# heatingHeader.net
KiCad netlist of a schematic drawn in EAGLE
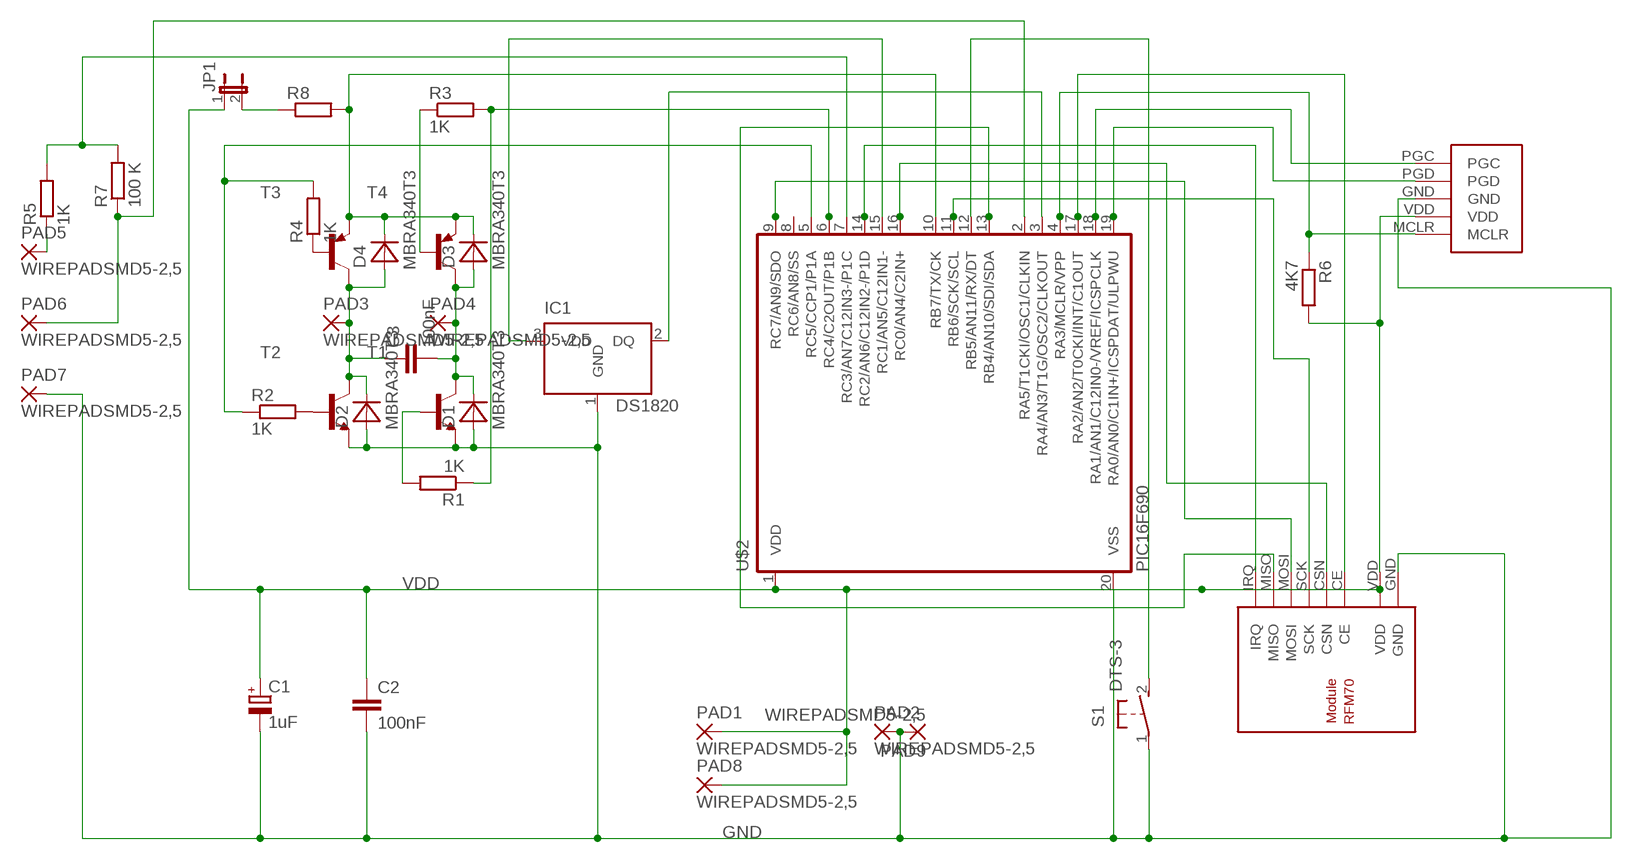
[diagram p0: schematic, sheet 1]

(export (version "E")
  (design (tool "Eeschema 10.0.6"))
  (components
    (comp (ref "C1")
      (value "1uF")
      (footprint "eagle-import:SMC_A")
      (libsource (lib "eagle-import") (part "CPOL-EUSMCA"))
    )
    (comp (ref "C2")
      (value "100nF")
      (footprint "eagle-import:C2012")
      (libsource (lib "eagle-import") (part "C-EUC2012"))
    )
    (comp (ref "C3")
      (value "100nF")
      (footprint "eagle-import:C2012")
      (libsource (lib "eagle-import") (part "C-EUC2012"))
    )
    (comp (ref "D1")
      (value "MBRA340T3")
      (footprint "eagle-import:SMA")
      (libsource (lib "eagle-import") (part "MBRA340T3"))
    )
    (comp (ref "D2")
      (value "MBRA340T3")
      (footprint "eagle-import:SMA")
      (libsource (lib "eagle-import") (part "MBRA340T3"))
    )
    (comp (ref "D3")
      (value "MBRA340T3")
      (footprint "eagle-import:SMA")
      (libsource (lib "eagle-import") (part "MBRA340T3"))
    )
    (comp (ref "D4")
      (value "MBRA340T3")
      (footprint "eagle-import:SMA")
      (libsource (lib "eagle-import") (part "MBRA340T3"))
    )
    (comp (ref "IC1")
      (value "DS1820")
      (footprint "eagle-import:TO-92")
      (libsource (lib "eagle-import") (part "DS1820"))
    )
    (comp (ref "JP1")
      (value "JP1E")
      (footprint "eagle-import:JP1")
      (libsource (lib "eagle-import") (part "JP1E"))
    )
    (comp (ref "PAD1")
      (value "WIREPADSMD5-2,5")
      (footprint "eagle-import:5-2,5")
      (libsource (lib "eagle-import") (part "WIREPADSMD5-2,5"))
    )
    (comp (ref "PAD2")
      (value "WIREPADSMD5-2,5")
      (footprint "eagle-import:5-2,5")
      (libsource (lib "eagle-import") (part "WIREPADSMD5-2,5"))
    )
    (comp (ref "PAD3")
      (value "WIREPADSMD5-2,5")
      (footprint "eagle-import:5-2,5")
      (libsource (lib "eagle-import") (part "WIREPADSMD5-2,5"))
    )
    (comp (ref "PAD4")
      (value "WIREPADSMD5-2,5")
      (footprint "eagle-import:5-2,5")
      (libsource (lib "eagle-import") (part "WIREPADSMD5-2,5"))
    )
    (comp (ref "PAD5")
      (value "WIREPADSMD5-2,5")
      (footprint "eagle-import:5-2,5")
      (libsource (lib "eagle-import") (part "WIREPADSMD5-2,5"))
    )
    (comp (ref "PAD6")
      (value "WIREPADSMD5-2,5")
      (footprint "eagle-import:5-2,5")
      (libsource (lib "eagle-import") (part "WIREPADSMD5-2,5"))
    )
    (comp (ref "PAD7")
      (value "WIREPADSMD5-2,5")
      (footprint "eagle-import:5-2,5")
      (libsource (lib "eagle-import") (part "WIREPADSMD5-2,5"))
    )
    (comp (ref "PAD8")
      (value "WIREPADSMD5-2,5")
      (footprint "eagle-import:5-2,5")
      (libsource (lib "eagle-import") (part "WIREPADSMD5-2,5"))
    )
    (comp (ref "PAD9")
      (value "WIREPADSMD5-2,5")
      (footprint "eagle-import:5-2,5")
      (libsource (lib "eagle-import") (part "WIREPADSMD5-2,5"))
    )
    (comp (ref "R1")
      (value "1K")
      (footprint "eagle-import:R1206")
      (libsource (lib "eagle-import") (part "R-EU_R1206"))
    )
    (comp (ref "R2")
      (value "1K")
      (footprint "eagle-import:R1206")
      (libsource (lib "eagle-import") (part "R-EU_R1206"))
    )
    (comp (ref "R3")
      (value "1K")
      (footprint "eagle-import:R1206")
      (libsource (lib "eagle-import") (part "R-EU_R1206"))
    )
    (comp (ref "R4")
      (value "1K")
      (footprint "eagle-import:R1206")
      (libsource (lib "eagle-import") (part "R-EU_R1206"))
    )
    (comp (ref "R5")
      (value "1K")
      (footprint "eagle-import:R1206")
      (libsource (lib "eagle-import") (part "R-EU_R1206"))
    )
    (comp (ref "R6")
      (value "4K7")
      (footprint "eagle-import:R1206W")
      (libsource (lib "eagle-import") (part "R-EU_R1206W"))
    )
    (comp (ref "R7")
      (value "100 K")
      (footprint "eagle-import:R1206")
      (libsource (lib "eagle-import") (part "R-EU_R1206"))
    )
    (comp (ref "R8")
      (value "R-EU_R2512W")
      (footprint "eagle-import:R2512W")
      (libsource (lib "eagle-import") (part "R-EU_R2512W"))
    )
    (comp (ref "S1")
      (value "DTS-3")
      (footprint "eagle-import:DTS-3")
      (libsource (lib "eagle-import") (part "DTS-3"))
    )
    (comp (ref "T1")
      (value "BC817-40-NPN-SOT23-BEC")
      (footprint "eagle-import:SOT23-BEC")
      (libsource (lib "eagle-import") (part "-NPN-SOT23-BECBC817-40"))
    )
    (comp (ref "T2")
      (value "BC817-40-NPN-SOT23-BEC")
      (footprint "eagle-import:SOT23-BEC")
      (libsource (lib "eagle-import") (part "-NPN-SOT23-BECBC817-40"))
    )
    (comp (ref "T3")
      (value "BC807-16-PNP-SOT23-BEC")
      (footprint "eagle-import:SOT23-BEC")
      (libsource (lib "eagle-import") (part "-PNP-SOT23-BECBC807-16"))
    )
    (comp (ref "T4")
      (value "BC807-16-PNP-SOT23-BEC")
      (footprint "eagle-import:SOT23-BEC")
      (libsource (lib "eagle-import") (part "-PNP-SOT23-BECBC807-16"))
    )
    (comp (ref "U$1")
      (value "RFM70")
      (footprint "eagle-import:RFM70")
      (libsource (lib "eagle-import") (part "RFM70"))
    )
    (comp (ref "U$2")
      (value "PIC16F690")
      (footprint "eagle-import:SSOP20")
      (libsource (lib "eagle-import") (part "PIC16F690"))
    )
    (comp (ref "U$3")
      (value "PROGRAMMINGHEADERDIP")
      (footprint "eagle-import:PROGHEADER")
      (libsource (lib "eagle-import") (part "PROGRAMMINGHEADERDIP"))
    )
  )
  (nets
    (net (code "1") (name "/GND") (class "Default")
      (node (ref "C1") (pin "-") (pinfunction "-_-") (pintype "passive"))
      (node (ref "C2") (pin "2") (pinfunction "2_2") (pintype "passive"))
      (node (ref "D1") (pin "A") (pinfunction "A_A") (pintype "passive"))
      (node (ref "D2") (pin "A") (pinfunction "A_A") (pintype "passive"))
      (node (ref "IC1") (pin "1") (pinfunction "GND_1") (pintype "power_in"))
      (node (ref "PAD2") (pin "1") (pinfunction "P_1") (pintype "passive"))
      (node (ref "PAD7") (pin "1") (pinfunction "P_1") (pintype "passive"))
      (node (ref "PAD9") (pin "1") (pinfunction "P_1") (pintype "passive"))
      (node (ref "S1") (pin "1") (pinfunction "1_1") (pintype "passive"))
      (node (ref "T1") (pin "E") (pinfunction "E_E") (pintype "passive"))
      (node (ref "T2") (pin "E") (pinfunction "E_E") (pintype "passive"))
      (node (ref "U$1") (pin "GND") (pinfunction "GND_GND") (pintype "power_in"))
      (node (ref "U$2") (pin "20") (pinfunction "VSS_20") (pintype "power_in"))
      (node (ref "U$3") (pin "GND") (pinfunction "GND_GND") (pintype "power_in"))
    )
    (net (code "2") (name "/VDD") (class "Default")
      (node (ref "C1") (pin "+") (pinfunction "+_+") (pintype "passive"))
      (node (ref "C2") (pin "1") (pinfunction "1_1") (pintype "passive"))
      (node (ref "JP1") (pin "1") (pinfunction "1_1") (pintype "passive"))
      (node (ref "PAD1") (pin "1") (pinfunction "P_1") (pintype "passive"))
      (node (ref "PAD8") (pin "1") (pinfunction "P_1") (pintype "passive"))
      (node (ref "R6") (pin "2") (pinfunction "2_2") (pintype "passive"))
      (node (ref "U$1") (pin "VDD") (pinfunction "VDD_VDD") (pintype "power_in"))
      (node (ref "U$2") (pin "1") (pinfunction "VDD_1") (pintype "power_in"))
      (node (ref "U$3") (pin "VDD") (pinfunction "VDD_VDD") (pintype "power_in"))
    )
    (net (code "3") (name "Net-(IC1-DQ)") (class "Default")
      (node (ref "IC1") (pin "2") (pinfunction "DQ_2") (pintype "output"))
      (node (ref "U$2") (pin "3") (pinfunction "RA4/AN3/T1G/OSC2/CLKOUT_3") (pintype "bidirectional"))
    )
    (net (code "4") (name "Net-(IC1-VDD)") (class "Default")
      (node (ref "IC1") (pin "3") (pinfunction "VDD_3") (pintype "input"))
      (node (ref "U$2") (pin "15") (pinfunction "RC1/AN5/C12IN1-_15") (pintype "bidirectional"))
    )
    (net (code "5") (name "Net-(JP1-Pad2)") (class "Default")
      (node (ref "JP1") (pin "2") (pinfunction "2_2") (pintype "passive"))
      (node (ref "R8") (pin "1") (pinfunction "1_1") (pintype "passive"))
    )
    (net (code "6") (name "Net-(PAD3-P)") (class "Default")
      (node (ref "C3") (pin "1") (pinfunction "1_1") (pintype "passive"))
      (node (ref "D2") (pin "C") (pinfunction "C_C") (pintype "passive"))
      (node (ref "D4") (pin "A") (pinfunction "A_A") (pintype "passive"))
      (node (ref "PAD3") (pin "1") (pinfunction "P_1") (pintype "passive"))
      (node (ref "T2") (pin "C") (pinfunction "C_C") (pintype "passive"))
      (node (ref "T3") (pin "C") (pinfunction "C_C") (pintype "passive"))
    )
    (net (code "7") (name "Net-(PAD4-P)") (class "Default")
      (node (ref "C3") (pin "2") (pinfunction "2_2") (pintype "passive"))
      (node (ref "D1") (pin "C") (pinfunction "C_C") (pintype "passive"))
      (node (ref "D3") (pin "A") (pinfunction "A_A") (pintype "passive"))
      (node (ref "PAD4") (pin "1") (pinfunction "P_1") (pintype "passive"))
      (node (ref "T1") (pin "C") (pinfunction "C_C") (pintype "passive"))
      (node (ref "T4") (pin "C") (pinfunction "C_C") (pintype "passive"))
    )
    (net (code "8") (name "Net-(PAD5-P)") (class "Default")
      (node (ref "PAD5") (pin "1") (pinfunction "P_1") (pintype "passive"))
      (node (ref "R5") (pin "1") (pinfunction "1_1") (pintype "passive"))
    )
    (net (code "9") (name "Net-(PAD6-P)") (class "Default")
      (node (ref "PAD6") (pin "1") (pinfunction "P_1") (pintype "passive"))
      (node (ref "R7") (pin "1") (pinfunction "1_1") (pintype "passive"))
      (node (ref "U$2") (pin "2") (pinfunction "RA5/T1CKI/OSC1/CLKIN_2") (pintype "bidirectional"))
    )
    (net (code "10") (name "Net-(R1-Pad2)") (class "Default")
      (node (ref "R1") (pin "2") (pinfunction "2_2") (pintype "passive"))
      (node (ref "T1") (pin "B") (pinfunction "B_B") (pintype "passive"))
    )
    (net (code "11") (name "Net-(R2-Pad2)") (class "Default")
      (node (ref "R2") (pin "2") (pinfunction "2_2") (pintype "passive"))
      (node (ref "T2") (pin "B") (pinfunction "B_B") (pintype "passive"))
    )
    (net (code "12") (name "Net-(R3-Pad1)") (class "Default")
      (node (ref "R3") (pin "1") (pinfunction "1_1") (pintype "passive"))
      (node (ref "T4") (pin "B") (pinfunction "B_B") (pintype "passive"))
    )
    (net (code "13") (name "Net-(R4-Pad1)") (class "Default")
      (node (ref "R4") (pin "1") (pinfunction "1_1") (pintype "passive"))
      (node (ref "T3") (pin "B") (pinfunction "B_B") (pintype "passive"))
    )
    (net (code "14") (name "Net-(U$2-RA0{slash}AN0{slash}C1IN+{slash}ICSPDAT{slash}ULPWU)") (class "Default")
      (node (ref "U$2") (pin "19") (pinfunction "RA0/AN0/C1IN+/ICSPDAT/ULPWU_19") (pintype "bidirectional"))
      (node (ref "U$3") (pin "PGD") (pinfunction "PGD_PGD") (pintype "bidirectional"))
    )
    (net (code "15") (name "Net-(U$2-RA1{slash}AN1{slash}C12IN0-{slash}VREF{slash}ICSPCLK)") (class "Default")
      (node (ref "U$2") (pin "18") (pinfunction "RA1/AN1/C12IN0-/VREF/ICSPCLK_18") (pintype "bidirectional"))
      (node (ref "U$3") (pin "PGC") (pinfunction "PGC_PGC") (pintype "bidirectional"))
    )
    (net (code "16") (name "Net-(U$2-RA2{slash}AN2{slash}T0CKI{slash}INT{slash}C1OUT)") (class "Default")
      (node (ref "U$1") (pin "CE") (pinfunction "CE_CE") (pintype "bidirectional"))
      (node (ref "U$2") (pin "17") (pinfunction "RA2/AN2/T0CKI/INT/C1OUT_17") (pintype "bidirectional"))
    )
    (net (code "17") (name "Net-(U$2-RA3{slash}MCLR{slash}VPP)") (class "Default")
      (node (ref "R6") (pin "1") (pinfunction "1_1") (pintype "passive"))
      (node (ref "U$2") (pin "4") (pinfunction "RA3/MCLR/VPP_4") (pintype "bidirectional"))
      (node (ref "U$3") (pin "MCLR") (pinfunction "MCLR_MCLR") (pintype "output"))
    )
    (net (code "18") (name "Net-(U$2-RB4{slash}AN10{slash}SDI{slash}SDA)") (class "Default")
      (node (ref "U$1") (pin "MISO") (pinfunction "MISO_MISO") (pintype "bidirectional"))
      (node (ref "U$2") (pin "13") (pinfunction "RB4/AN10/SDI/SDA_13") (pintype "bidirectional"))
    )
    (net (code "19") (name "Net-(U$2-RB5{slash}AN11{slash}RX{slash}DT)") (class "Default")
      (node (ref "S1") (pin "2") (pinfunction "2_2") (pintype "passive"))
      (node (ref "U$2") (pin "12") (pinfunction "RB5/AN11/RX/DT_12") (pintype "bidirectional"))
    )
    (net (code "20") (name "Net-(U$2-RB6{slash}SCK{slash}SCL)") (class "Default")
      (node (ref "U$1") (pin "SCK") (pinfunction "SCK_SCK") (pintype "bidirectional"))
      (node (ref "U$2") (pin "11") (pinfunction "RB6/SCK/SCL_11") (pintype "bidirectional"))
    )
    (net (code "21") (name "Net-(U$2-RB7{slash}TX{slash}CK)") (class "Default")
      (node (ref "D3") (pin "C") (pinfunction "C_C") (pintype "passive"))
      (node (ref "D4") (pin "C") (pinfunction "C_C") (pintype "passive"))
      (node (ref "R8") (pin "2") (pinfunction "2_2") (pintype "passive"))
      (node (ref "T3") (pin "E") (pinfunction "E_E") (pintype "passive"))
      (node (ref "T4") (pin "E") (pinfunction "E_E") (pintype "passive"))
      (node (ref "U$2") (pin "10") (pinfunction "RB7/TX/CK_10") (pintype "bidirectional"))
    )
    (net (code "22") (name "Net-(U$2-RC0{slash}AN4{slash}C2IN+)") (class "Default")
      (node (ref "U$1") (pin "CSN") (pinfunction "CSN_CSN") (pintype "bidirectional"))
      (node (ref "U$2") (pin "16") (pinfunction "RC0/AN4/C2IN+_16") (pintype "bidirectional"))
    )
    (net (code "23") (name "Net-(U$2-RC2{slash}AN6{slash}C12IN2-{slash}P1D)") (class "Default")
      (node (ref "U$1") (pin "IRQ") (pinfunction "IRQ_IRQ") (pintype "bidirectional"))
      (node (ref "U$2") (pin "14") (pinfunction "RC2/AN6/C12IN2-/P1D_14") (pintype "bidirectional"))
    )
    (net (code "24") (name "Net-(U$2-RC3{slash}AN7C12IN3-{slash}P1C)") (class "Default")
      (node (ref "R5") (pin "2") (pinfunction "2_2") (pintype "passive"))
      (node (ref "R7") (pin "2") (pinfunction "2_2") (pintype "passive"))
      (node (ref "U$2") (pin "7") (pinfunction "RC3/AN7C12IN3-/P1C_7") (pintype "bidirectional"))
    )
    (net (code "25") (name "Net-(U$2-RC4{slash}C2OUT{slash}P1B)") (class "Default")
      (node (ref "R1") (pin "1") (pinfunction "1_1") (pintype "passive"))
      (node (ref "R3") (pin "2") (pinfunction "2_2") (pintype "passive"))
      (node (ref "U$2") (pin "6") (pinfunction "RC4/C2OUT/P1B_6") (pintype "bidirectional"))
    )
    (net (code "26") (name "Net-(U$2-RC5{slash}CCP1{slash}P1A)") (class "Default")
      (node (ref "R2") (pin "1") (pinfunction "1_1") (pintype "passive"))
      (node (ref "R4") (pin "2") (pinfunction "2_2") (pintype "passive"))
      (node (ref "U$2") (pin "5") (pinfunction "RC5/CCP1/P1A_5") (pintype "bidirectional"))
    )
    (net (code "27") (name "Net-(U$2-RC7{slash}AN9{slash}SDO)") (class "Default")
      (node (ref "U$1") (pin "MOSI") (pinfunction "MOSI_MOSI") (pintype "bidirectional"))
      (node (ref "U$2") (pin "9") (pinfunction "RC7/AN9/SDO_9") (pintype "bidirectional"))
    )
    (net (code "28") (name "unconnected-(U$2-RC6{slash}AN8{slash}SS-Pad8)") (class "Default")
      (node (ref "U$2") (pin "8") (pinfunction "RC6/AN8/SS_8") (pintype "bidirectional"))
    )
  )
)
